# fabflash-mk-2_1-booster.net
KiCad netlist of a schematic drawn in EAGLE
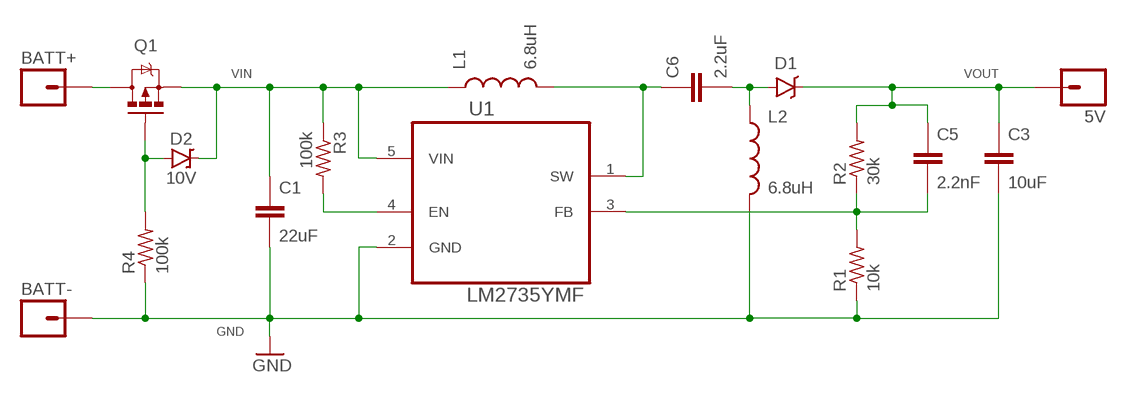
[diagram p0: schematic, sheet 1]

(export (version "E")
  (design (tool "Eeschema 10.0.6"))
  (components
    (comp (ref "5V")
      (value "M01PTH-1.2MM")
      (footprint "eagle-import:1X01-1.2MM")
      (libsource (lib "eagle-import") (part "M01PTH-1.2MM"))
    )
    (comp (ref "BATT+")
      (value "M01NOT-A-VIA-NOPE")
      (footprint "eagle-import:1X01_NOSILK_NOSTOP")
      (libsource (lib "eagle-import") (part "M01NOT-A-VIA-NOPE"))
    )
    (comp (ref "BATT-")
      (value "M01NOT-A-VIA-NOPE")
      (footprint "eagle-import:1X01_NOSILK_NOSTOP")
      (libsource (lib "eagle-import") (part "M01NOT-A-VIA-NOPE"))
    )
    (comp (ref "C1")
      (value "22uF")
      (footprint "eagle-import:C0805")
      (libsource (lib "eagle-import") (part "CAPACITOR-CERAMICC0805"))
    )
    (comp (ref "C3")
      (value "10uF")
      (footprint "eagle-import:C0805")
      (libsource (lib "eagle-import") (part "CAPACITOR-CERAMICC0805"))
    )
    (comp (ref "C5")
      (value "2.2nF")
      (footprint "eagle-import:C0805")
      (libsource (lib "eagle-import") (part "CAPACITOR-CERAMICC0805"))
    )
    (comp (ref "C6")
      (value "2.2uF")
      (footprint "eagle-import:C0805")
      (libsource (lib "eagle-import") (part "CAPACITOR-CERAMICC0805"))
    )
    (comp (ref "D1")
      (value "B340A")
      (footprint "eagle-import:SMA-DIODE")
      (libsource (lib "eagle-import") (part "DIODE-SCHOTTKYB340A"))
    )
    (comp (ref "D2")
      (value "10V")
      (footprint "eagle-import:SOD123")
      (libsource (lib "eagle-import") (part "DIODE-ZENERSOD123"))
    )
    (comp (ref "L1")
      (value "6.8uH")
      (footprint "eagle-import:TAIYO-YUDEN-40XX")
      (libsource (lib "eagle-import") (part "INDUCTORTAIYO-YUDEN-40XX"))
    )
    (comp (ref "L2")
      (value "6.8uH")
      (footprint "eagle-import:TAIYO-YUDEN-40XX")
      (libsource (lib "eagle-import") (part "INDUCTORTAIYO-YUDEN-40XX"))
    )
    (comp (ref "Q1")
      (value "MOSFET-PCHANNELIRLML2244")
      (footprint "eagle-import:SOT23-3")
      (libsource (lib "eagle-import") (part "MOSFET-PCHANNELIRLML2244"))
    )
    (comp (ref "R1")
      (value "10k")
      (footprint "eagle-import:R0805")
      (libsource (lib "eagle-import") (part "RESISTORR0805"))
    )
    (comp (ref "R2")
      (value "30k")
      (footprint "eagle-import:R0805")
      (libsource (lib "eagle-import") (part "RESISTORR0805"))
    )
    (comp (ref "R3")
      (value "100k")
      (footprint "eagle-import:R0603")
      (libsource (lib "eagle-import") (part "RESISTORR0603"))
    )
    (comp (ref "R4")
      (value "100k")
      (footprint "eagle-import:R0603")
      (libsource (lib "eagle-import") (part "RESISTORR0603"))
    )
    (comp (ref "U1")
      (value "LM2735YMF")
      (footprint "eagle-import:SOT95P285X110-5N")
      (libsource (lib "eagle-import") (part "LM2735YMF"))
    )
  )
  (nets
    (net (code "1") (name "/VIN") (class "Default")
      (node (ref "C1") (pin "1") (pinfunction "1_1") (pintype "passive"))
      (node (ref "D2") (pin "C") (pinfunction "C_C") (pintype "passive"))
      (node (ref "L1") (pin "1") (pinfunction "1_1") (pintype "passive"))
      (node (ref "Q1") (pin "2") (pinfunction "S_2") (pintype "passive"))
      (node (ref "R3") (pin "1") (pinfunction "1_1") (pintype "passive"))
      (node (ref "U1") (pin "5") (pinfunction "VIN_5") (pintype "power_in"))
    )
    (net (code "2") (name "/VOUT") (class "Default")
      (node (ref "5V") (pin "P$1") (pinfunction "1_P$1") (pintype "passive"))
      (node (ref "C3") (pin "1") (pinfunction "1_1") (pintype "passive"))
      (node (ref "C5") (pin "1") (pinfunction "1_1") (pintype "passive"))
      (node (ref "D1") (pin "C") (pinfunction "C_C") (pintype "passive"))
      (node (ref "R2") (pin "2") (pinfunction "2_2") (pintype "passive"))
    )
    (net (code "3") (name "GND") (class "Default")
      (node (ref "BATT-") (pin "P$1") (pinfunction "1_P$1") (pintype "passive"))
      (node (ref "C1") (pin "2") (pinfunction "2_2") (pintype "passive"))
      (node (ref "C3") (pin "2") (pinfunction "2_2") (pintype "passive"))
      (node (ref "L2") (pin "2") (pinfunction "2_2") (pintype "passive"))
      (node (ref "R1") (pin "1") (pinfunction "1_1") (pintype "passive"))
      (node (ref "R4") (pin "1") (pinfunction "1_1") (pintype "passive"))
      (node (ref "U1") (pin "2") (pinfunction "GND_2") (pintype "power_in"))
    )
    (net (code "4") (name "Net-(BATT+-1)") (class "Default")
      (node (ref "BATT+") (pin "P$1") (pinfunction "1_P$1") (pintype "passive"))
      (node (ref "Q1") (pin "3") (pinfunction "D_3") (pintype "passive"))
    )
    (net (code "5") (name "Net-(C6-Pad2)") (class "Default")
      (node (ref "C6") (pin "2") (pinfunction "2_2") (pintype "passive"))
      (node (ref "D1") (pin "A") (pinfunction "A_A") (pintype "passive"))
      (node (ref "L2") (pin "1") (pinfunction "1_1") (pintype "passive"))
    )
    (net (code "6") (name "Net-(Q1-G)") (class "Default")
      (node (ref "D2") (pin "A") (pinfunction "A_A") (pintype "passive"))
      (node (ref "Q1") (pin "1") (pinfunction "G_1") (pintype "passive"))
      (node (ref "R4") (pin "2") (pinfunction "2_2") (pintype "passive"))
    )
    (net (code "7") (name "Net-(U1-EN)") (class "Default")
      (node (ref "R3") (pin "2") (pinfunction "2_2") (pintype "passive"))
      (node (ref "U1") (pin "4") (pinfunction "EN_4") (pintype "input"))
    )
    (net (code "8") (name "Net-(U1-FB)") (class "Default")
      (node (ref "C5") (pin "2") (pinfunction "2_2") (pintype "passive"))
      (node (ref "R1") (pin "2") (pinfunction "2_2") (pintype "passive"))
      (node (ref "R2") (pin "1") (pinfunction "1_1") (pintype "passive"))
      (node (ref "U1") (pin "3") (pinfunction "FB_3") (pintype "input"))
    )
    (net (code "9") (name "Net-(U1-SW)") (class "Default")
      (node (ref "C6") (pin "1") (pinfunction "1_1") (pintype "passive"))
      (node (ref "L1") (pin "2") (pinfunction "2_2") (pintype "passive"))
      (node (ref "U1") (pin "1") (pinfunction "SW_1") (pintype "power_in"))
    )
  )
)
